# Input.net
KiCad netlist of a schematic drawn in Altium Designer
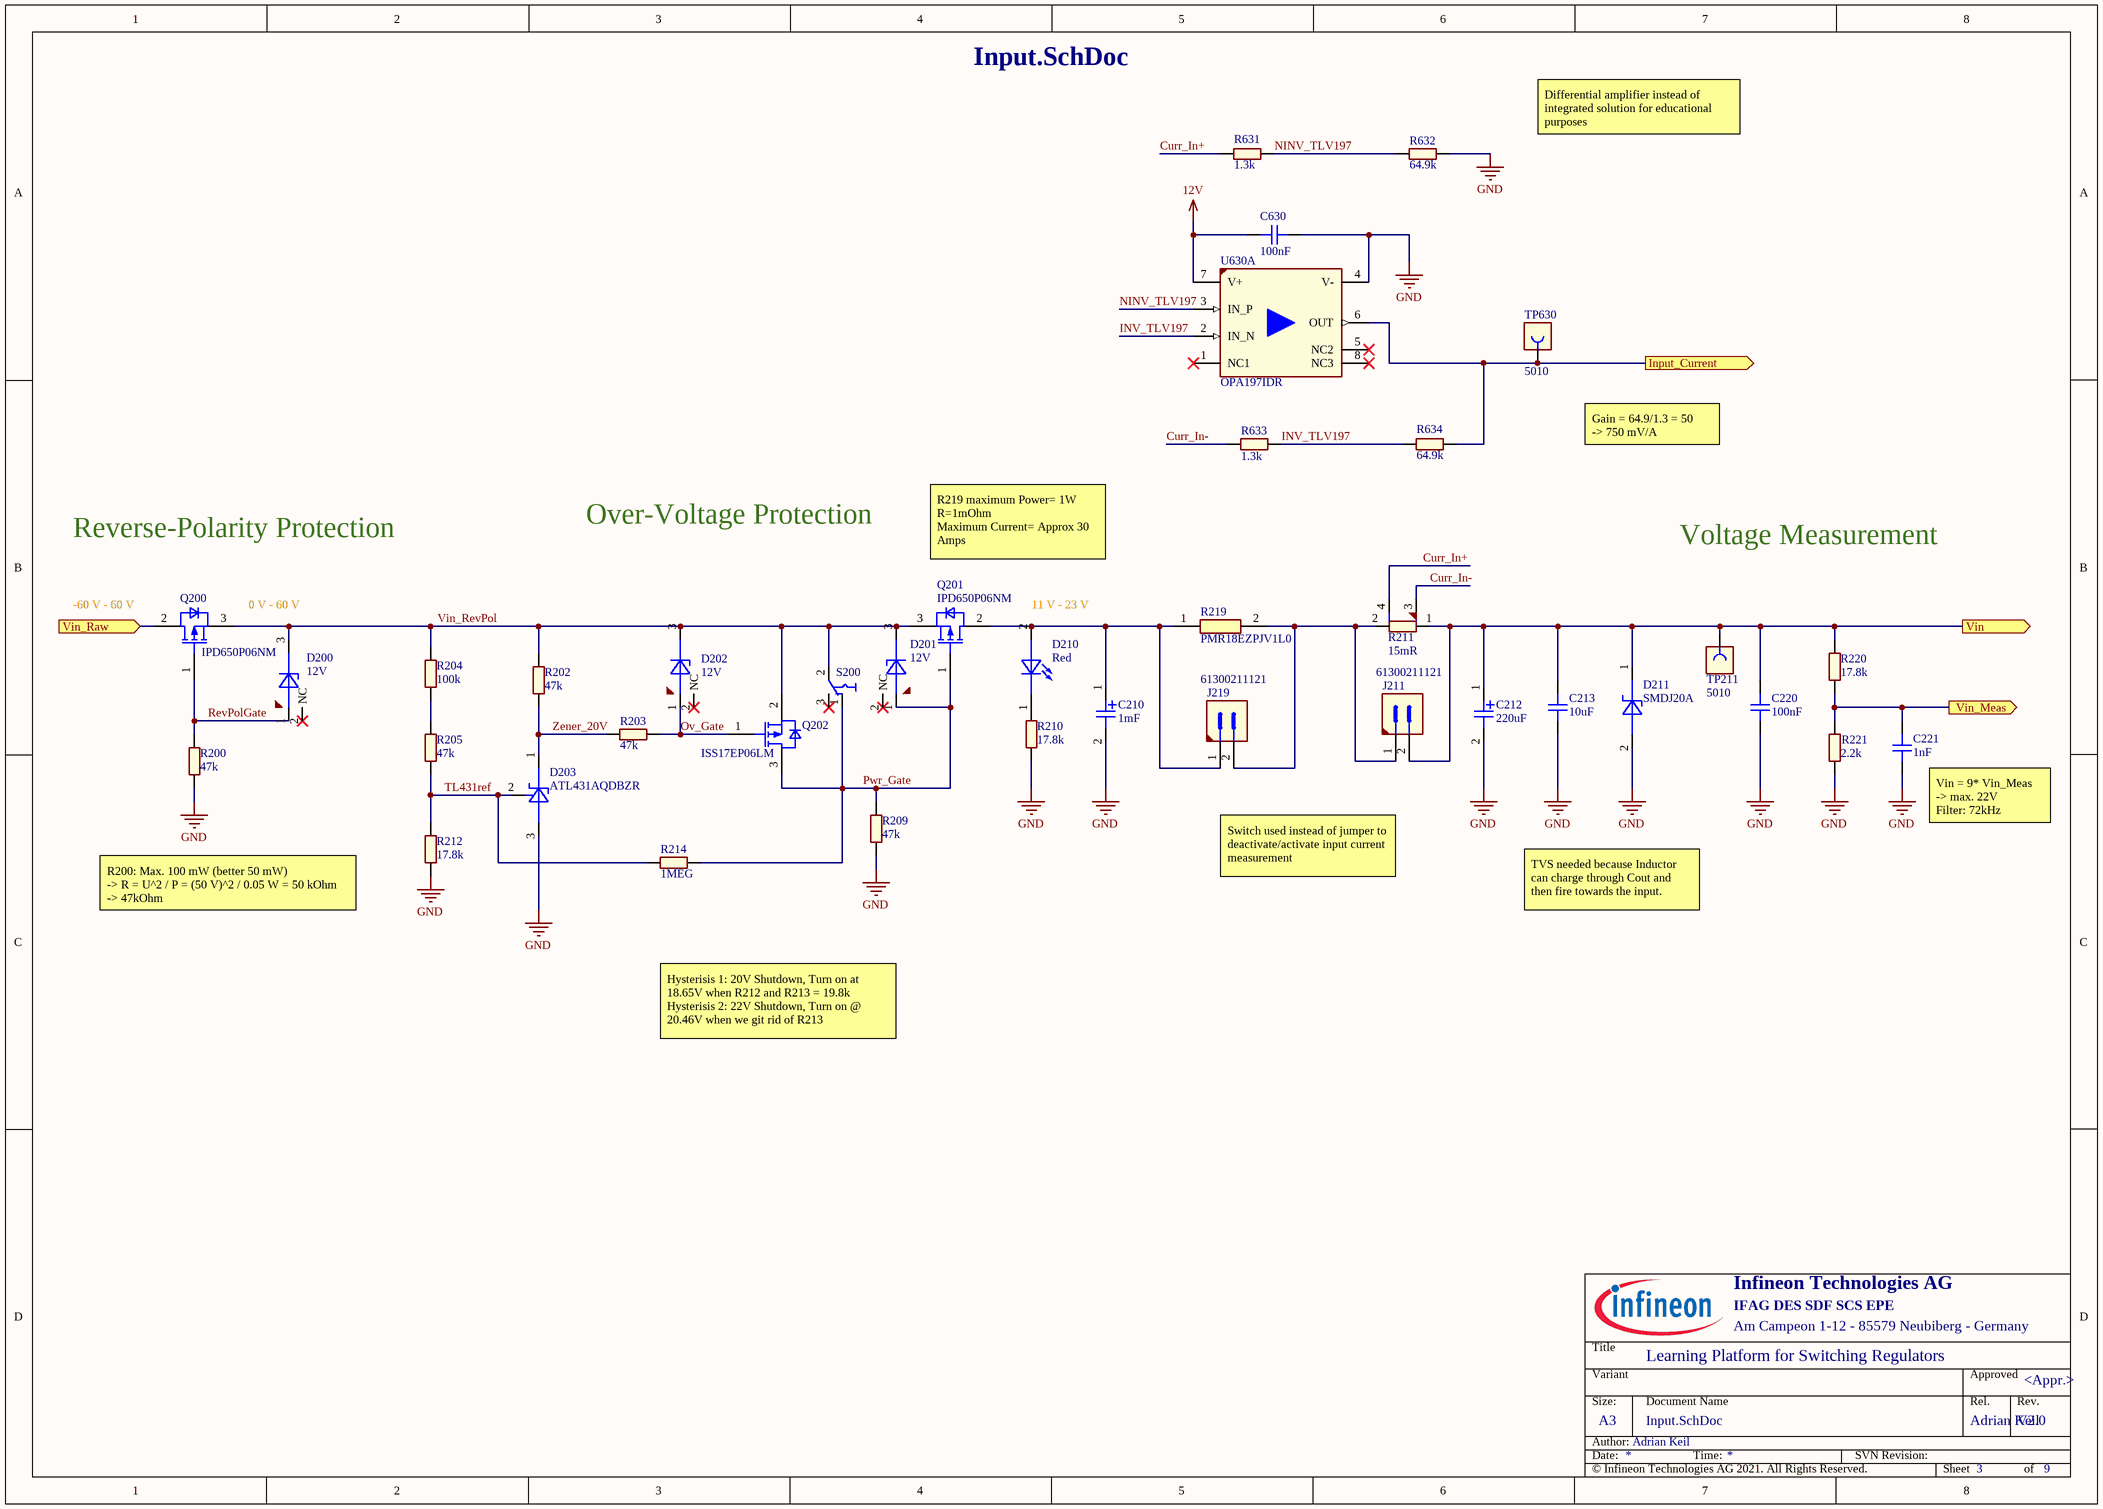
[diagram p0: Input.SchDoc]

(export (version "E")
  (design (tool "Eeschema 10.0.6"))
  (components
    (comp (ref "C210")
      (value "1mF")
      (footprint "CAPPRD500W60D1300H2700B")
      (fields (field (name "MANUFACTURER") "Kemet"))
      (libsource (lib "PCBLibraryData") (part "CAP-SGL-POL-02P_00000002"))
    )
    (comp (ref "C212")
      (value "220uF")
      (footprint "CAPAE1030X1050N-3")
      (fields (field (name "MANUFACTURER") "Nippon Chemi-Con"))
      (libsource (lib "PCBLibraryData") (part "CAP-SGL-POL-02P_00000002"))
    )
    (comp (ref "C213")
      (value "10uF")
      (footprint "CAPC3216X190N-1")
      (description "CAP / CERA / 10uF / 50V / 20% / X5R (EIA) / -55°C to 85°C / 1206 (3216) / SMD / -")
      (fields (field (name "MANUFACTURER") "Taiyo Yuden"))
      (libsource (lib "PCBLibraryData") (part "CAP-SGL-STD-02P_00000001"))
    )
    (comp (ref "C220")
      (value "100nF")
      (footprint "CAPC3216X125N-0")
      (description "CAP / CERA / 100nF / 50V / 10% / X7R (EIA) / -55°C to 125°C / 1206(3216) / SMD / -")
      (fields (field (name "LEGACY PARTNUMBER") "CAP01005660") (field (name "MANUFACTURER") "MuRata"))
      (libsource (lib "PCBLibraryData") (part "CAP-SGL-STD-02P_00000001"))
    )
    (comp (ref "C221")
      (value "1nF")
      (footprint "CAPC3216X95N")
      (description "CAP / CERA / 1nF / 50V / 10% / X7R (EIA) / -55°C to 125°C / 1206(3216) / SMD / -")
      (fields (field (name "LEGACY PARTNUMBER") "CAP01005183") (field (name "MANUFACTURER") "MuRata"))
      (libsource (lib "PCBLibraryData") (part "CAP-SGL-STD-02P_00000001"))
    )
    (comp (ref "C630")
      (value "100nF")
      (footprint "CAPC3216X125N-0")
      (description "CAP / CERA / 100nF / 50V / 10% / X7R (EIA) / -55°C to 125°C / 1206(3216) / SMD / -")
      (fields (field (name "LEGACY PARTNUMBER") "CAP01005660") (field (name "MANUFACTURER") "MuRata"))
      (libsource (lib "PCBLibraryData") (part "CAP-SGL-STD-02P_00000001"))
    )
    (comp (ref "D200")
      (value "12V")
      (footprint "SOT95P230X110-3N")
      (description "Voltage regulator diodes")
      (fields (field (name "MANUFACTURER") "Nexperia"))
      (libsource (lib "PCBLibraryData") (part "d_zener_a1c3_3p"))
    )
    (comp (ref "D201")
      (value "12V")
      (footprint "SOT95P230X110-3N")
      (description "Voltage regulator diodes")
      (fields (field (name "MANUFACTURER") "Nexperia"))
      (libsource (lib "PCBLibraryData") (part "d_zener_a1c3_3p"))
    )
    (comp (ref "D202")
      (value "12V")
      (footprint "SOT95P230X110-3N")
      (description "Voltage regulator diodes")
      (fields (field (name "MANUFACTURER") "Nexperia"))
      (libsource (lib "PCBLibraryData") (part "d_zener_a1c3_3p"))
    )
    (comp (ref "D203")
      (value "ATL431AQDBZR")
      (footprint "SOT95P237X112-3N-1")
      (description "ATL431 Adjustable Precision Shunt Regulator")
      (fields (field (name "MANUFACTURER") "Texas Instruments"))
      (libsource (lib "PCBLibraryData") (part "d_tvs_c1a3_3p"))
    )
    (comp (ref "D210")
      (value "Red")
      (footprint "LEDSC160X80X80-2N-1")
      (description "WL-SMCW SMT Mono-color Chip LED Waterclear, Red,630nm")
      (fields (field (name "MANUFACTURER") "Wurth Elektronik"))
      (libsource (lib "PCBLibraryData") (part "d_led_a"))
    )
    (comp (ref "D211")
      (value "SMDJ20A")
      (footprint "DIOM7959X262N")
      (description "TVS Diode, Low Profile Package, Built in Strain Relief, Glass Passivated Chip Junction")
      (fields (field (name "MANUFACTURER") "Littelfuse"))
      (libsource (lib "PCBLibraryData") (part "d_tvs_a"))
    )
    (comp (ref "J211")
      (value "61300211121")
      (footprint "CON-M-THT-61300211121")
      (description "Header, 2.54mm Pitch, 2 pin, Vertical, Single Row")
      (fields
        (field (name "LEGACY PARTNUMBER") "CON01500943")
        (field (name "MANUFACTURER") "Wurth Elektronik")
      )
      (libsource (lib "PCBLibraryData") (part "Header 2"))
    )
    (comp (ref "J219")
      (value "61300211121")
      (footprint "CON-M-THT-61300211121")
      (description "Header, 2.54mm Pitch, 2 pin, Vertical, Single Row")
      (fields
        (field (name "LEGACY PARTNUMBER") "CON01500943")
        (field (name "MANUFACTURER") "Wurth Elektronik")
      )
      (libsource (lib "PCBLibraryData") (part "Header 2"))
    )
    (comp (ref "Q200")
      (value "IPD650P06NM")
      (footprint "TO228P998X250-3N-V2")
      (description "OptiMOS Power Transistor, -60 V")
      (fields (field (name "MANUFACTURER") "Infineon Technologies"))
      (libsource (lib "PCBLibraryData") (part "igfet_p_ch_enh_dio_1g2d3s_3p"))
    )
    (comp (ref "Q201")
      (value "IPD650P06NM")
      (footprint "TO228P998X250-3N-V2")
      (description "OptiMOS Power Transistor, -60 V")
      (fields (field (name "MANUFACTURER") "Infineon Technologies"))
      (libsource (lib "PCBLibraryData") (part "igfet_p_ch_enh_dio_1g2d3s_3p"))
    )
    (comp (ref "Q202")
      (value "ISS17EP06LM")
      (footprint "SOT95P240X110-3N-1-V")
      (description "OptiMOSTM Small Signal Transistor, -60 V")
      (fields (field (name "MANUFACTURER") "Infineon Technologies"))
      (libsource (lib "PCBLibraryData") (part "igfet_p_ch_enh_dio_1g2s3d_3p"))
    )
    (comp (ref "R200")
      (value "47k")
      (footprint "RESC3216X60N")
      (description "RES / STD / 47k / 250mW / 1% / 100ppm/K / -55°C to 155°C / 1206(3216) / SMD / -")
      (fields (field (name "LEGACY PARTNUMBER") "RES01802933") (field (name "MANUFACTURER") "Vishay"))
      (libsource (lib "PCBLibraryData") (part "RES-SGL-STD-02P_00000006"))
    )
    (comp (ref "R202")
      (value "47k")
      (footprint "RESC3216X60N")
      (description "RES / STD / 47k / 250mW / 1% / 100ppm/K / -55°C to 155°C / 1206(3216) / SMD / -")
      (fields (field (name "LEGACY PARTNUMBER") "RES01802933") (field (name "MANUFACTURER") "Vishay"))
      (libsource (lib "PCBLibraryData") (part "RES-SGL-STD-02P_00000006"))
    )
    (comp (ref "R203")
      (value "47k")
      (footprint "RESC3216X60N")
      (description "RES / STD / 47k / 250mW / 1% / 100ppm/K / -55°C to 155°C / 1206(3216) / SMD / -")
      (fields (field (name "LEGACY PARTNUMBER") "RES01802933") (field (name "MANUFACTURER") "Vishay"))
      (libsource (lib "") (part "RES-SGL-STD-02P_00000006_1"))
    )
    (comp (ref "R204")
      (value "100k")
      (footprint "RESC3216X60N")
      (description "RES / STD / 100k / 250mW / 1% / 100ppm/K / -55°C to 155°C / 1206(3216) / SMD / -")
      (fields (field (name "LEGACY PARTNUMBER") "RES01802971") (field (name "MANUFACTURER") "Vishay"))
      (libsource (lib "") (part "RES-SGL-STD-02P_00000006_2"))
    )
    (comp (ref "R205")
      (value "47k")
      (footprint "RESC3216X60N")
      (description "RES / STD / 47k / 250mW / 1% / 100ppm/K / -55°C to 155°C / 1206(3216) / SMD / -")
      (fields (field (name "LEGACY PARTNUMBER") "RES01802933") (field (name "MANUFACTURER") "Vishay"))
      (libsource (lib "PCBLibraryData") (part "RES-SGL-STD-02P_00000006"))
    )
    (comp (ref "R209")
      (value "47k")
      (footprint "RESC3216X60N")
      (description "RES / STD / 47k / 250mW / 1% / 100ppm/K / -55°C to 155°C / 1206(3216) / SMD / -")
      (fields (field (name "LEGACY PARTNUMBER") "RES01802933") (field (name "MANUFACTURER") "Vishay"))
      (libsource (lib "PCBLibraryData") (part "RES-SGL-STD-02P_00000006"))
    )
    (comp (ref "R210")
      (value "17.8k")
      (footprint "RESC3216X60N")
      (description "RES / STD / 17.8k / 250mW / 1% / 100ppm/K / -55°C to 155°C / 1206(3216) / SMD / -")
      (fields (field (name "LEGACY PARTNUMBER") "RES01802883") (field (name "MANUFACTURER") "Vishay"))
      (libsource (lib "") (part "RES-SGL-STD-02P_00000006_2"))
    )
    (comp (ref "R211")
      (value "15mR")
      (footprint "RES-SMD-L4T12")
      (description "RES / STD / 15mR / 500mW / 1% / 75ppm/K / -55°C to 155°C / 1206 (3216) / SMD / -")
      (fields (field (name "MANUFACTURER") "Ohmite"))
      (libsource (lib "PCBLibraryData") (part "RES-SHT-STD-04P_00097BE5"))
    )
    (comp (ref "R212")
      (value "17.8k")
      (footprint "RESC3216X60N")
      (description "RES / STD / 17.8k / 250mW / 1% / 100ppm/K / -55°C to 155°C / 1206(3216) / SMD / -")
      (fields (field (name "LEGACY PARTNUMBER") "RES01802883") (field (name "MANUFACTURER") "Vishay"))
      (libsource (lib "") (part "RES-SGL-STD-02P_00000006_2"))
    )
    (comp (ref "R214")
      (value "1MEG")
      (footprint "RESC3216X60N")
      (description "RES / STD / 1MEG / 250mW / 1% / 100ppm/K / -55°C to 155°C / 1206(3216) / SMD / -")
      (fields (field (name "LEGACY PARTNUMBER") "RES01803085") (field (name "MANUFACTURER") "Vishay"))
      (libsource (lib "") (part "RES-SGL-STD-02P_00000006_3"))
    )
    (comp (ref "R219")
      (value "PMR18EZPJV1L0")
      (footprint "SamacSys:RESC3216X59N")
      (description "Resistor")
      (fields (field (name "MOUSER PART NUMBER") "755-PMR18EZPJV1L0"))
      (libsource (lib "*") (part "PMR18EZPJV1L0"))
    )
    (comp (ref "R220")
      (value "17.8k")
      (footprint "RESC3216X60N")
      (description "RES / STD / 17.8k / 250mW / 1% / 100ppm/K / -55°C to 155°C / 1206(3216) / SMD / -")
      (fields (field (name "LEGACY PARTNUMBER") "RES01802883") (field (name "MANUFACTURER") "Vishay"))
      (libsource (lib "") (part "RES-SGL-STD-02P_00000006_2"))
    )
    (comp (ref "R221")
      (value "2.2k")
      (footprint "RESC3216X60N")
      (description "RES / STD / 2.2k / 250mW / 1% / 100ppm/K / -55°C to 155°C / 1206(3216) / SMD / -")
      (fields (field (name "LEGACY PARTNUMBER") "RES01802779") (field (name "MANUFACTURER") "Vishay"))
      (libsource (lib "") (part "RES-SGL-STD-02P_00000006_2"))
    )
    (comp (ref "R631")
      (value "1.3k")
      (footprint "RESC3216X60N")
      (description "RES / STD / 1.3k / 250mW / 1% / 100ppm/K / -55°C to 155°C / 1206(3216) / SMD / -")
      (fields (field (name "LEGACY PARTNUMBER") "RES01802755") (field (name "MANUFACTURER") "Vishay"))
      (libsource (lib "") (part "RES-SGL-STD-02P_00000006_3"))
    )
    (comp (ref "R632")
      (value "64.9k")
      (footprint "RESC3216X60N")
      (description "RES / STD / 64.9k / 250mW / 1% / 100ppm/K / -55°C to 155°C / 1206(3216) / SMD / -")
      (fields (field (name "LEGACY PARTNUMBER") "RES01802950") (field (name "MANUFACTURER") "Vishay"))
      (libsource (lib "") (part "RES-SGL-STD-02P_00000006_3"))
    )
    (comp (ref "R633")
      (value "1.3k")
      (footprint "RESC3216X60N")
      (description "RES / STD / 1.3k / 250mW / 1% / 100ppm/K / -55°C to 155°C / 1206(3216) / SMD / -")
      (fields (field (name "LEGACY PARTNUMBER") "RES01802755") (field (name "MANUFACTURER") "Vishay"))
      (libsource (lib "") (part "RES-SGL-STD-02P_00000006_3"))
    )
    (comp (ref "R634")
      (value "64.9k")
      (footprint "RESC3216X60N")
      (description "RES / STD / 64.9k / 250mW / 1% / 100ppm/K / -55°C to 155°C / 1206(3216) / SMD / -")
      (fields (field (name "LEGACY PARTNUMBER") "RES01802950") (field (name "MANUFACTURER") "Vishay"))
      (libsource (lib "") (part "RES-SGL-STD-02P_00000006_3"))
    )
    (comp (ref "S200")
      (value "CL-SB-12A-01T")
      (footprint "SW-SMD-CL-SB-12A-01T")
      (description "Slid Switch, 12V, 200mA")
      (fields (field (name "MANUFACTURER") "NIDEC COPAL ELECTRONICS, Inc."))
      (libsource (lib "PCBLibraryData") (part "sw_co213_3p"))
    )
    (comp (ref "TP211")
      (value "5010")
      (footprint "CON-THT-TP-5010")
      (description "PC Test Point-Multipurpose THT, Red")
      (fields
        (field (name "LEGACY PARTNUMBER") "CON01500529")
        (field (name "MANUFACTURER") "Keystone Electronics Corp.")
      )
      (libsource (lib "PCBLibraryData") (part "connector_1_f"))
    )
    (comp (ref "TP630")
      (value "5010")
      (footprint "CON-THT-TP-5010")
      (description "PC Test Point-Multipurpose THT, Red")
      (fields
        (field (name "LEGACY PARTNUMBER") "CON01500529")
        (field (name "MANUFACTURER") "Keystone Electronics Corp.")
      )
      (libsource (lib "") (part "connector_1_f_1"))
    )
    (comp (ref "U630")
      (value "OPA197IDR")
      (footprint "SOIC127P600X175-8N-23")
      (fields (field (name "MANUFACTURER") "Texas Instruments"))
      (libsource (lib "PCBLibraryData") (part "OPA140AID"))
    )
  )
  (nets
    (net (code "1") (name "/Curr_In+") (class "Default")
      (node (ref "R211") (pin "4") (pinfunction "I2_4") (pintype "passive"))
      (node (ref "R631") (pin "1") (pinfunction "1_1") (pintype "passive"))
    )
    (net (code "2") (name "/Curr_In-") (class "Default")
      (node (ref "R211") (pin "3") (pinfunction "I1_3") (pintype "passive"))
      (node (ref "R633") (pin "1") (pinfunction "1_1") (pintype "passive"))
    )
    (net (code "3") (name "/INV_TLV197") (class "Default")
      (node (ref "R633") (pin "2") (pinfunction "2_2") (pintype "passive"))
      (node (ref "R634") (pin "1") (pinfunction "1_1") (pintype "passive"))
      (node (ref "U630") (pin "2") (pinfunction "IN_N_2") (pintype "input"))
    )
    (net (code "4") (name "/Input_Current") (class "Default")
      (node (ref "R634") (pin "2") (pinfunction "2_2") (pintype "passive"))
      (node (ref "TP630") (pin "1") (pinfunction "1_1") (pintype "passive"))
      (node (ref "U630") (pin "6") (pinfunction "OUT_6") (pintype "output"))
    )
    (net (code "5") (name "/NINV_TLV197") (class "Default")
      (node (ref "R631") (pin "2") (pinfunction "2_2") (pintype "passive"))
      (node (ref "R632") (pin "1") (pinfunction "1_1") (pintype "passive"))
      (node (ref "U630") (pin "3") (pinfunction "IN_P_3") (pintype "input"))
    )
    (net (code "6") (name "/Ov_Gate") (class "Default")
      (node (ref "D202") (pin "1") (pinfunction "ANODE_1") (pintype "passive"))
      (node (ref "Q202") (pin "1") (pinfunction "GATE_1") (pintype "passive"))
      (node (ref "R203") (pin "1") (pinfunction "1_1") (pintype "passive"))
    )
    (net (code "7") (name "/Pwr_Gate") (class "Default")
      (node (ref "D201") (pin "1") (pinfunction "ANODE_1") (pintype "passive"))
      (node (ref "Q201") (pin "1") (pinfunction "GATE_1") (pintype "passive"))
      (node (ref "Q202") (pin "3") (pinfunction "DRAIN_3") (pintype "passive"))
      (node (ref "R209") (pin "2") (pinfunction "2_2") (pintype "passive"))
      (node (ref "R214") (pin "2") (pinfunction "2_2") (pintype "passive"))
      (node (ref "S200") (pin "1") (pinfunction "1_1") (pintype "passive"))
    )
    (net (code "8") (name "/RevPolGate") (class "Default")
      (node (ref "D200") (pin "1") (pinfunction "ANODE_1") (pintype "passive"))
      (node (ref "Q200") (pin "1") (pinfunction "GATE_1") (pintype "passive"))
      (node (ref "R200") (pin "2") (pinfunction "2_2") (pintype "passive"))
    )
    (net (code "9") (name "/TL431ref") (class "Default")
      (node (ref "D203") (pin "2") (pinfunction "REF_2") (pintype "passive"))
      (node (ref "R205") (pin "1") (pinfunction "1_1") (pintype "passive"))
      (node (ref "R212") (pin "1") (pinfunction "1_1") (pintype "passive"))
      (node (ref "R214") (pin "1") (pinfunction "1_1") (pintype "passive"))
    )
    (net (code "10") (name "/Vin") (class "Default")
      (node (ref "C212") (pin "1") (pinfunction "1_1") (pintype "passive"))
      (node (ref "C213") (pin "2") (pinfunction "2_2") (pintype "passive"))
      (node (ref "C220") (pin "1") (pinfunction "1_1") (pintype "passive"))
      (node (ref "D211") (pin "1") (pinfunction "CATHODE_1") (pintype "passive"))
      (node (ref "J211") (pin "2") (pinfunction "2_2") (pintype "passive"))
      (node (ref "R211") (pin "1") (pinfunction "V1_1") (pintype "passive"))
      (node (ref "R220") (pin "1") (pinfunction "1_1") (pintype "passive"))
      (node (ref "TP211") (pin "1") (pinfunction "1_1") (pintype "passive"))
    )
    (net (code "11") (name "/Vin_Meas") (class "Default")
      (node (ref "C221") (pin "2") (pinfunction "2_2") (pintype "passive"))
      (node (ref "R220") (pin "2") (pinfunction "2_2") (pintype "passive"))
      (node (ref "R221") (pin "1") (pinfunction "1_1") (pintype "passive"))
    )
    (net (code "12") (name "/Vin_Raw") (class "Default")
      (node (ref "Q200") (pin "2") (pinfunction "DRAIN_2") (pintype "passive"))
    )
    (net (code "13") (name "/Vin_RevPol") (class "Default")
      (node (ref "D200") (pin "3") (pinfunction "CATHODE_3") (pintype "passive"))
      (node (ref "D201") (pin "3") (pinfunction "CATHODE_3") (pintype "passive"))
      (node (ref "D202") (pin "3") (pinfunction "CATHODE_3") (pintype "passive"))
      (node (ref "Q200") (pin "3") (pinfunction "SOURCE_3") (pintype "passive"))
      (node (ref "Q201") (pin "3") (pinfunction "SOURCE_3") (pintype "passive"))
      (node (ref "Q202") (pin "2") (pinfunction "SOURCE_2") (pintype "passive"))
      (node (ref "R202") (pin "2") (pinfunction "2_2") (pintype "passive"))
      (node (ref "R204") (pin "1") (pinfunction "1_1") (pintype "passive"))
      (node (ref "S200") (pin "2") (pinfunction "2_2") (pintype "passive"))
    )
    (net (code "14") (name "/Zener_20V") (class "Default")
      (node (ref "D203") (pin "1") (pinfunction "CATHODE_1") (pintype "passive"))
      (node (ref "R202") (pin "1") (pinfunction "1_1") (pintype "passive"))
      (node (ref "R203") (pin "2") (pinfunction "2_2") (pintype "passive"))
    )
    (net (code "15") (name "12V") (class "Default")
      (node (ref "C630") (pin "2") (pinfunction "2_2") (pintype "passive"))
      (node (ref "U630") (pin "7") (pinfunction "V+_7") (pintype "power_in"))
    )
    (net (code "16") (name "GND") (class "Default")
      (node (ref "C210") (pin "2") (pinfunction "2_2") (pintype "passive"))
      (node (ref "C212") (pin "2") (pinfunction "2_2") (pintype "passive"))
      (node (ref "C213") (pin "1") (pinfunction "1_1") (pintype "passive"))
      (node (ref "C220") (pin "2") (pinfunction "2_2") (pintype "passive"))
      (node (ref "C221") (pin "1") (pinfunction "1_1") (pintype "passive"))
      (node (ref "C630") (pin "1") (pinfunction "1_1") (pintype "passive"))
      (node (ref "D203") (pin "3") (pinfunction "ANODE_3") (pintype "passive"))
      (node (ref "D211") (pin "2") (pinfunction "ANODE_2") (pintype "passive"))
      (node (ref "R200") (pin "1") (pinfunction "1_1") (pintype "passive"))
      (node (ref "R209") (pin "1") (pinfunction "1_1") (pintype "passive"))
      (node (ref "R210") (pin "2") (pinfunction "2_2") (pintype "passive"))
      (node (ref "R212") (pin "2") (pinfunction "2_2") (pintype "passive"))
      (node (ref "R221") (pin "2") (pinfunction "2_2") (pintype "passive"))
      (node (ref "R632") (pin "2") (pinfunction "2_2") (pintype "passive"))
      (node (ref "U630") (pin "4") (pinfunction "V-_4") (pintype "power_in"))
    )
    (net (code "17") (name "Net-(D210-Anode)") (class "Default")
      (node (ref "C210") (pin "1") (pinfunction "1_1") (pintype "passive"))
      (node (ref "D210") (pin "2") (pinfunction "Anode_2") (pintype "passive"))
      (node (ref "J219") (pin "1") (pinfunction "1_1") (pintype "passive"))
      (node (ref "Q201") (pin "2") (pinfunction "DRAIN_2") (pintype "passive"))
      (node (ref "R219") (pin "1") (pinfunction "1_1") (pintype "passive"))
    )
    (net (code "18") (name "Net-(D210-Cathode)") (class "Default")
      (node (ref "D210") (pin "1") (pinfunction "Cathode_1") (pintype "passive"))
      (node (ref "R210") (pin "1") (pinfunction "1_1") (pintype "passive"))
    )
    (net (code "19") (name "Net-(R204-Pad2)") (class "Default")
      (node (ref "R204") (pin "2") (pinfunction "2_2") (pintype "passive"))
      (node (ref "R205") (pin "2") (pinfunction "2_2") (pintype "passive"))
    )
    (net (code "20") (name "Net-(R211-V2)") (class "Default")
      (node (ref "J211") (pin "1") (pinfunction "1_1") (pintype "passive"))
      (node (ref "J219") (pin "2") (pinfunction "2_2") (pintype "passive"))
      (node (ref "R211") (pin "2") (pinfunction "V2_2") (pintype "passive"))
      (node (ref "R219") (pin "2") (pinfunction "2_2") (pintype "passive"))
    )
    (net (code "21") (name "unconnected-(D200-NC-Pad2)") (class "Default")
      (node (ref "D200") (pin "2") (pinfunction "NC_2") (pintype "passive+no_connect"))
    )
    (net (code "22") (name "unconnected-(D201-NC-Pad2)") (class "Default")
      (node (ref "D201") (pin "2") (pinfunction "NC_2") (pintype "passive+no_connect"))
    )
    (net (code "23") (name "unconnected-(D202-NC-Pad2)") (class "Default")
      (node (ref "D202") (pin "2") (pinfunction "NC_2") (pintype "passive+no_connect"))
    )
    (net (code "24") (name "unconnected-(S200-Pad3)") (class "Default")
      (node (ref "S200") (pin "3") (pinfunction "3_3") (pintype "passive+no_connect"))
    )
    (net (code "25") (name "unconnected-(U630-NC1-Pad1)") (class "Default")
      (node (ref "U630") (pin "1") (pinfunction "NC1_1") (pintype "passive+no_connect"))
    )
    (net (code "26") (name "unconnected-(U630-NC2-Pad5)") (class "Default")
      (node (ref "U630") (pin "5") (pinfunction "NC2_5") (pintype "passive+no_connect"))
    )
    (net (code "27") (name "unconnected-(U630-NC3-Pad8)") (class "Default")
      (node (ref "U630") (pin "8") (pinfunction "NC3_8") (pintype "passive+no_connect"))
    )
  )
)
